# weather.net
KiCad netlist of a schematic drawn in EAGLE
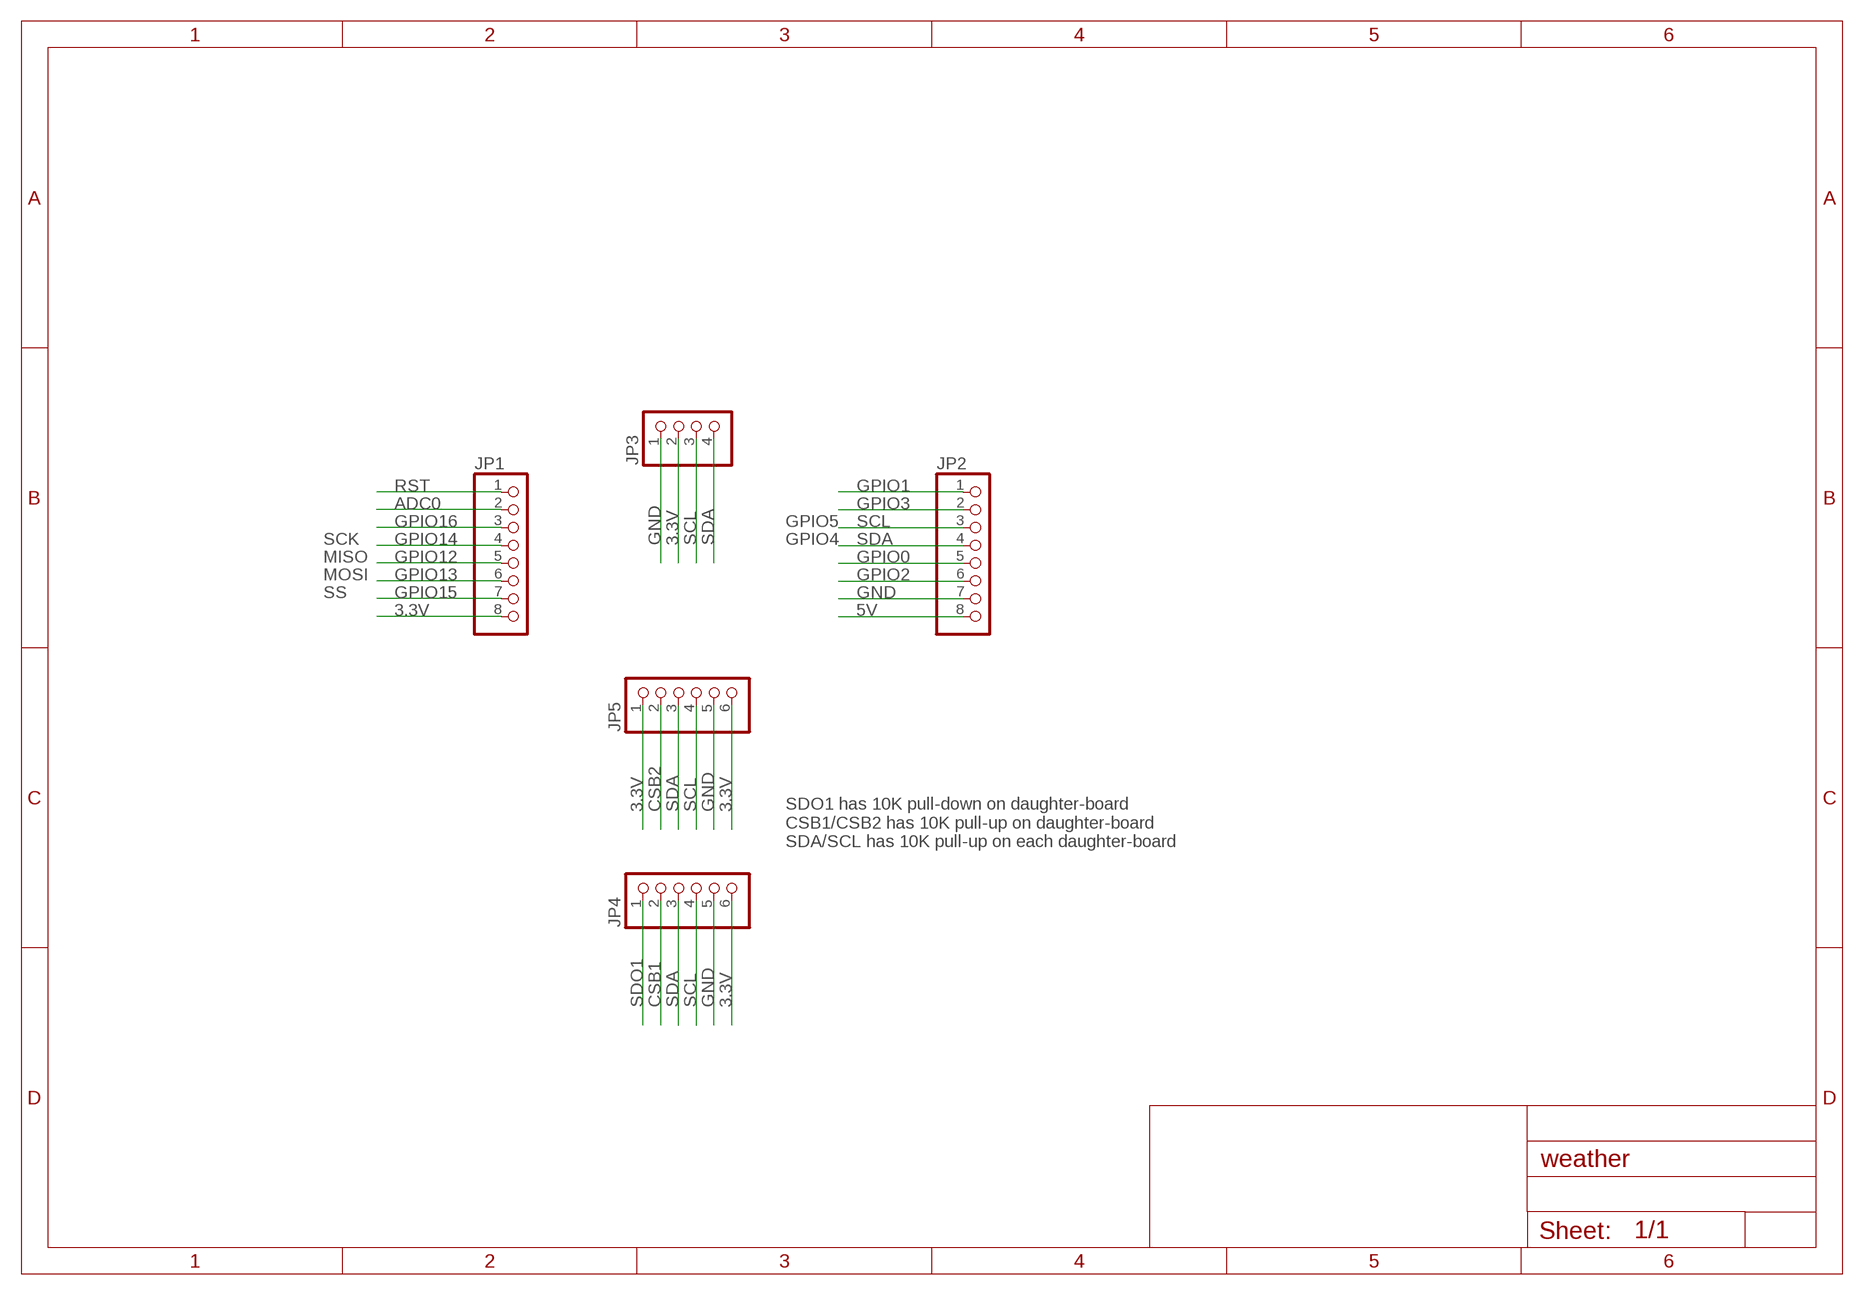
[diagram p0: schematic, sheet 1]

(export (version "E")
  (design (tool "Eeschema 10.0.6"))
  (components
    (comp (ref "JP1")
      (value "PINHD-1X8")
      (footprint "eagle-import:1X08")
      (libsource (lib "eagle-import") (part "PINHD-1X8"))
    )
    (comp (ref "JP2")
      (value "PINHD-1X8")
      (footprint "eagle-import:1X08")
      (libsource (lib "eagle-import") (part "PINHD-1X8"))
    )
    (comp (ref "JP3")
      (value "PINHD-1X4")
      (footprint "eagle-import:1X04")
      (libsource (lib "eagle-import") (part "PINHD-1X4"))
    )
    (comp (ref "JP4")
      (value "PINHD-1X6")
      (footprint "eagle-import:1X06")
      (libsource (lib "eagle-import") (part "PINHD-1X6"))
    )
    (comp (ref "JP5")
      (value "PINHD-1X6")
      (footprint "eagle-import:1X06")
      (libsource (lib "eagle-import") (part "PINHD-1X6"))
    )
  )
  (nets
    (net (code "1") (name "/3.3V") (class "Default")
      (node (ref "JP1") (pin "8") (pinfunction "8_8") (pintype "passive"))
      (node (ref "JP3") (pin "2") (pinfunction "2_2") (pintype "passive"))
      (node (ref "JP4") (pin "6") (pinfunction "6_6") (pintype "passive"))
      (node (ref "JP5") (pin "1") (pinfunction "1_1") (pintype "passive"))
      (node (ref "JP5") (pin "6") (pinfunction "6_6") (pintype "passive"))
    )
    (net (code "2") (name "/5V") (class "Default")
      (node (ref "JP2") (pin "8") (pinfunction "8_8") (pintype "passive"))
    )
    (net (code "3") (name "/ADC0") (class "Default")
      (node (ref "JP1") (pin "2") (pinfunction "2_2") (pintype "passive"))
    )
    (net (code "4") (name "/CSB1") (class "Default")
      (node (ref "JP4") (pin "2") (pinfunction "2_2") (pintype "passive"))
    )
    (net (code "5") (name "/CSB2") (class "Default")
      (node (ref "JP5") (pin "2") (pinfunction "2_2") (pintype "passive"))
    )
    (net (code "6") (name "/GND") (class "Default")
      (node (ref "JP2") (pin "7") (pinfunction "7_7") (pintype "passive"))
      (node (ref "JP3") (pin "1") (pinfunction "1_1") (pintype "passive"))
      (node (ref "JP4") (pin "5") (pinfunction "5_5") (pintype "passive"))
      (node (ref "JP5") (pin "5") (pinfunction "5_5") (pintype "passive"))
    )
    (net (code "7") (name "/GPIO0") (class "Default")
      (node (ref "JP2") (pin "5") (pinfunction "5_5") (pintype "passive"))
    )
    (net (code "8") (name "/GPIO1") (class "Default")
      (node (ref "JP2") (pin "1") (pinfunction "1_1") (pintype "passive"))
    )
    (net (code "9") (name "/GPIO2") (class "Default")
      (node (ref "JP2") (pin "6") (pinfunction "6_6") (pintype "passive"))
    )
    (net (code "10") (name "/GPIO3") (class "Default")
      (node (ref "JP2") (pin "2") (pinfunction "2_2") (pintype "passive"))
    )
    (net (code "11") (name "/GPIO12") (class "Default")
      (node (ref "JP1") (pin "5") (pinfunction "5_5") (pintype "passive"))
    )
    (net (code "12") (name "/GPIO13") (class "Default")
      (node (ref "JP1") (pin "6") (pinfunction "6_6") (pintype "passive"))
    )
    (net (code "13") (name "/GPIO14") (class "Default")
      (node (ref "JP1") (pin "4") (pinfunction "4_4") (pintype "passive"))
    )
    (net (code "14") (name "/GPIO15") (class "Default")
      (node (ref "JP1") (pin "7") (pinfunction "7_7") (pintype "passive"))
    )
    (net (code "15") (name "/GPIO16") (class "Default")
      (node (ref "JP1") (pin "3") (pinfunction "3_3") (pintype "passive"))
    )
    (net (code "16") (name "/RST") (class "Default")
      (node (ref "JP1") (pin "1") (pinfunction "1_1") (pintype "passive"))
    )
    (net (code "17") (name "/SCL") (class "Default")
      (node (ref "JP2") (pin "3") (pinfunction "3_3") (pintype "passive"))
      (node (ref "JP3") (pin "3") (pinfunction "3_3") (pintype "passive"))
      (node (ref "JP4") (pin "4") (pinfunction "4_4") (pintype "passive"))
      (node (ref "JP5") (pin "4") (pinfunction "4_4") (pintype "passive"))
    )
    (net (code "18") (name "/SDA") (class "Default")
      (node (ref "JP2") (pin "4") (pinfunction "4_4") (pintype "passive"))
      (node (ref "JP3") (pin "4") (pinfunction "4_4") (pintype "passive"))
      (node (ref "JP4") (pin "3") (pinfunction "3_3") (pintype "passive"))
      (node (ref "JP5") (pin "3") (pinfunction "3_3") (pintype "passive"))
    )
    (net (code "19") (name "/SDO1") (class "Default")
      (node (ref "JP4") (pin "1") (pinfunction "1_1") (pintype "passive"))
    )
  )
)
